# GB_TSOP44_ROM_ADAPTER_c.net
KiCad netlist of a schematic drawn in EAGLE
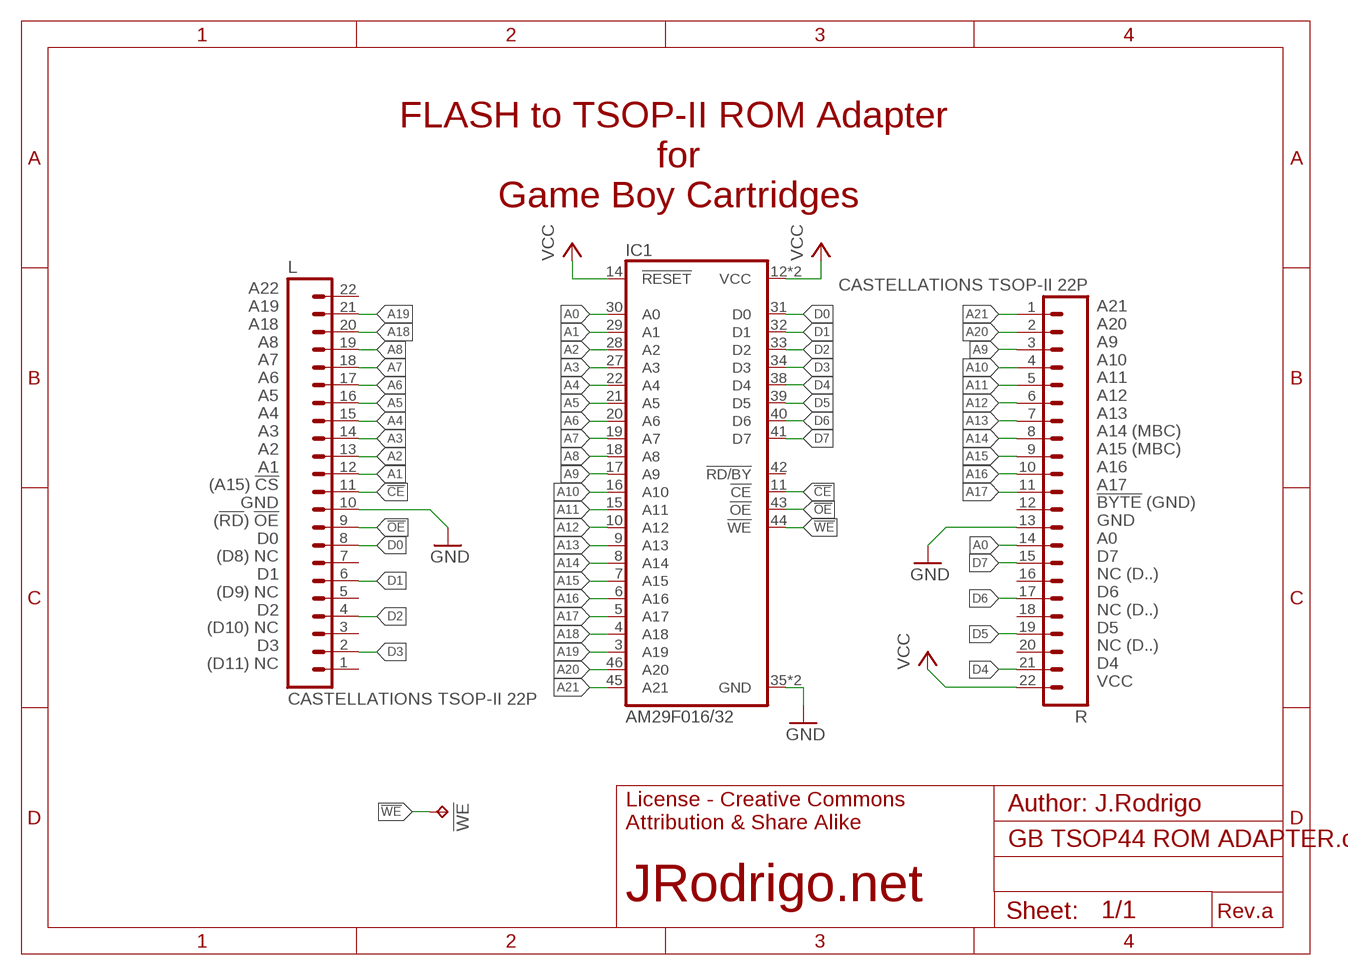
[diagram p0: schematic, sheet 1]

(export (version "E")
  (design (tool "Eeschema 10.0.6"))
  (components
    (comp (ref "!WE")
      (value "TPTP06SQ")
      (footprint "eagle-import:TP06SQ")
      (libsource (lib "eagle-import") (part "TPTP06SQ"))
    )
    (comp (ref "IC1")
      (value "AM29F016/32")
      (footprint "eagle-import:TSOP48-2")
      (libsource (lib "eagle-import") (part "AM29FXXXCUSTOM"))
    )
    (comp (ref "L")
      (value "CASTELLATIONS TSOP-II 22P")
      (footprint "eagle-import:CASTELLATIONS_TSOP_II_22PHH")
      (libsource (lib "eagle-import") (part "CASTELLATIONS_TSOP-II-22PHH"))
    )
    (comp (ref "R")
      (value "CASTELLATIONS TSOP-II 22P")
      (footprint "eagle-import:CASTELLATIONS_TSOP_II_22PHH")
      (libsource (lib "eagle-import") (part "CASTELLATIONS_TSOP-II-22PHH"))
    )
  )
  (nets
    (net (code "1") (name "/~{CE}") (class "Default")
      (node (ref "IC1") (pin "11") (pinfunction "~{CE}_11") (pintype "input"))
      (node (ref "L") (pin "11") (pinfunction "11_11") (pintype "passive"))
    )
    (net (code "2") (name "/~{OE}") (class "Default")
      (node (ref "IC1") (pin "43") (pinfunction "~{OE}_43") (pintype "input"))
      (node (ref "L") (pin "9") (pinfunction "9_9") (pintype "passive"))
    )
    (net (code "3") (name "/~{WE}") (class "Default")
      (node (ref "!WE") (pin "TP") (pinfunction "TP_TP") (pintype "input"))
      (node (ref "IC1") (pin "44") (pinfunction "~{WE}_44") (pintype "input"))
    )
    (net (code "4") (name "A0") (class "Default")
      (node (ref "IC1") (pin "30") (pinfunction "A0_30") (pintype "input"))
      (node (ref "R") (pin "14") (pinfunction "14_14") (pintype "passive"))
    )
    (net (code "5") (name "A1") (class "Default")
      (node (ref "IC1") (pin "29") (pinfunction "A1_29") (pintype "input"))
      (node (ref "L") (pin "12") (pinfunction "12_12") (pintype "passive"))
    )
    (net (code "6") (name "A2") (class "Default")
      (node (ref "IC1") (pin "28") (pinfunction "A2_28") (pintype "input"))
      (node (ref "L") (pin "13") (pinfunction "13_13") (pintype "passive"))
    )
    (net (code "7") (name "A3") (class "Default")
      (node (ref "IC1") (pin "27") (pinfunction "A3_27") (pintype "input"))
      (node (ref "L") (pin "14") (pinfunction "14_14") (pintype "passive"))
    )
    (net (code "8") (name "A4") (class "Default")
      (node (ref "IC1") (pin "22") (pinfunction "A4_22") (pintype "input"))
      (node (ref "L") (pin "15") (pinfunction "15_15") (pintype "passive"))
    )
    (net (code "9") (name "A5") (class "Default")
      (node (ref "IC1") (pin "21") (pinfunction "A5_21") (pintype "input"))
      (node (ref "L") (pin "16") (pinfunction "16_16") (pintype "passive"))
    )
    (net (code "10") (name "A6") (class "Default")
      (node (ref "IC1") (pin "20") (pinfunction "A6_20") (pintype "input"))
      (node (ref "L") (pin "17") (pinfunction "17_17") (pintype "passive"))
    )
    (net (code "11") (name "A7") (class "Default")
      (node (ref "IC1") (pin "19") (pinfunction "A7_19") (pintype "input"))
      (node (ref "L") (pin "18") (pinfunction "18_18") (pintype "passive"))
    )
    (net (code "12") (name "A8") (class "Default")
      (node (ref "IC1") (pin "18") (pinfunction "A8_18") (pintype "input"))
      (node (ref "L") (pin "19") (pinfunction "19_19") (pintype "passive"))
    )
    (net (code "13") (name "A9") (class "Default")
      (node (ref "IC1") (pin "17") (pinfunction "A9_17") (pintype "input"))
      (node (ref "R") (pin "3") (pinfunction "3_3") (pintype "passive"))
    )
    (net (code "14") (name "A10") (class "Default")
      (node (ref "IC1") (pin "16") (pinfunction "A10_16") (pintype "input"))
      (node (ref "R") (pin "4") (pinfunction "4_4") (pintype "passive"))
    )
    (net (code "15") (name "A11") (class "Default")
      (node (ref "IC1") (pin "15") (pinfunction "A11_15") (pintype "input"))
      (node (ref "R") (pin "5") (pinfunction "5_5") (pintype "passive"))
    )
    (net (code "16") (name "A12") (class "Default")
      (node (ref "IC1") (pin "10") (pinfunction "A12_10") (pintype "input"))
      (node (ref "R") (pin "6") (pinfunction "6_6") (pintype "passive"))
    )
    (net (code "17") (name "A13") (class "Default")
      (node (ref "IC1") (pin "9") (pinfunction "A13_9") (pintype "input"))
      (node (ref "R") (pin "7") (pinfunction "7_7") (pintype "passive"))
    )
    (net (code "18") (name "A14") (class "Default")
      (node (ref "IC1") (pin "8") (pinfunction "A14_8") (pintype "input"))
      (node (ref "R") (pin "8") (pinfunction "8_8") (pintype "passive"))
    )
    (net (code "19") (name "A15") (class "Default")
      (node (ref "IC1") (pin "7") (pinfunction "A15_7") (pintype "input"))
      (node (ref "R") (pin "9") (pinfunction "9_9") (pintype "passive"))
    )
    (net (code "20") (name "A16") (class "Default")
      (node (ref "IC1") (pin "6") (pinfunction "A16_6") (pintype "input"))
      (node (ref "R") (pin "10") (pinfunction "10_10") (pintype "passive"))
    )
    (net (code "21") (name "A17") (class "Default")
      (node (ref "IC1") (pin "5") (pinfunction "A17_5") (pintype "input"))
      (node (ref "R") (pin "11") (pinfunction "11_11") (pintype "passive"))
    )
    (net (code "22") (name "A18") (class "Default")
      (node (ref "IC1") (pin "4") (pinfunction "A18_4") (pintype "input"))
      (node (ref "L") (pin "20") (pinfunction "20_20") (pintype "passive"))
    )
    (net (code "23") (name "A19") (class "Default")
      (node (ref "IC1") (pin "3") (pinfunction "A19_3") (pintype "input"))
      (node (ref "L") (pin "21") (pinfunction "21_21") (pintype "passive"))
    )
    (net (code "24") (name "A20") (class "Default")
      (node (ref "IC1") (pin "46") (pinfunction "A20_46") (pintype "input"))
      (node (ref "R") (pin "2") (pinfunction "2_2") (pintype "passive"))
    )
    (net (code "25") (name "A21") (class "Default")
      (node (ref "IC1") (pin "45") (pinfunction "A21_45") (pintype "input"))
      (node (ref "R") (pin "1") (pinfunction "1_1") (pintype "passive"))
    )
    (net (code "26") (name "D0") (class "Default")
      (node (ref "IC1") (pin "31") (pinfunction "D0_31") (pintype "tri_state"))
      (node (ref "L") (pin "8") (pinfunction "8_8") (pintype "passive"))
    )
    (net (code "27") (name "D1") (class "Default")
      (node (ref "IC1") (pin "32") (pinfunction "D1_32") (pintype "tri_state"))
      (node (ref "L") (pin "6") (pinfunction "6_6") (pintype "passive"))
    )
    (net (code "28") (name "D2") (class "Default")
      (node (ref "IC1") (pin "33") (pinfunction "D2_33") (pintype "tri_state"))
      (node (ref "L") (pin "4") (pinfunction "4_4") (pintype "passive"))
    )
    (net (code "29") (name "D3") (class "Default")
      (node (ref "IC1") (pin "34") (pinfunction "D3_34") (pintype "tri_state"))
      (node (ref "L") (pin "2") (pinfunction "2_2") (pintype "passive"))
    )
    (net (code "30") (name "D4") (class "Default")
      (node (ref "IC1") (pin "38") (pinfunction "D4_38") (pintype "tri_state"))
      (node (ref "R") (pin "21") (pinfunction "21_21") (pintype "passive"))
    )
    (net (code "31") (name "D5") (class "Default")
      (node (ref "IC1") (pin "39") (pinfunction "D5_39") (pintype "tri_state"))
      (node (ref "R") (pin "19") (pinfunction "19_19") (pintype "passive"))
    )
    (net (code "32") (name "D6") (class "Default")
      (node (ref "IC1") (pin "40") (pinfunction "D6_40") (pintype "tri_state"))
      (node (ref "R") (pin "17") (pinfunction "17_17") (pintype "passive"))
    )
    (net (code "33") (name "D7") (class "Default")
      (node (ref "IC1") (pin "41") (pinfunction "D7_41") (pintype "tri_state"))
      (node (ref "R") (pin "15") (pinfunction "15_15") (pintype "passive"))
    )
    (net (code "34") (name "GND") (class "Default")
      (node (ref "IC1") (pin "35") (pinfunction "GND_35") (pintype "power_in"))
      (node (ref "IC1") (pin "36") (pinfunction "GND_36") (pintype "power_in"))
      (node (ref "L") (pin "10") (pinfunction "10_10") (pintype "passive"))
      (node (ref "R") (pin "13") (pinfunction "13_13") (pintype "passive"))
    )
    (net (code "35") (name "VCC") (class "Default")
      (node (ref "IC1") (pin "12") (pinfunction "VCC_12") (pintype "power_in"))
      (node (ref "IC1") (pin "14") (pinfunction "~{RESET}_14") (pintype "input"))
      (node (ref "IC1") (pin "37") (pinfunction "VCC_37") (pintype "power_in"))
      (node (ref "R") (pin "22") (pinfunction "22_22") (pintype "passive"))
    )
    (net (code "36") (name "unconnected-(IC1-~{RD{slash}BY}-Pad42)") (class "Default")
      (node (ref "IC1") (pin "42") (pinfunction "~{RD/BY}_42") (pintype "output"))
    )
    (net (code "37") (name "unconnected-(L-Pad1)") (class "Default")
      (node (ref "L") (pin "1") (pinfunction "1_1") (pintype "passive"))
    )
    (net (code "38") (name "unconnected-(L-Pad3)") (class "Default")
      (node (ref "L") (pin "3") (pinfunction "3_3") (pintype "passive"))
    )
    (net (code "39") (name "unconnected-(L-Pad5)") (class "Default")
      (node (ref "L") (pin "5") (pinfunction "5_5") (pintype "passive"))
    )
    (net (code "40") (name "unconnected-(L-Pad7)") (class "Default")
      (node (ref "L") (pin "7") (pinfunction "7_7") (pintype "passive"))
    )
    (net (code "41") (name "unconnected-(L-Pad22)") (class "Default")
      (node (ref "L") (pin "22") (pinfunction "22_22") (pintype "passive"))
    )
    (net (code "42") (name "unconnected-(R-Pad12)") (class "Default")
      (node (ref "R") (pin "12") (pinfunction "12_12") (pintype "passive"))
    )
    (net (code "43") (name "unconnected-(R-Pad16)") (class "Default")
      (node (ref "R") (pin "16") (pinfunction "16_16") (pintype "passive"))
    )
    (net (code "44") (name "unconnected-(R-Pad18)") (class "Default")
      (node (ref "R") (pin "18") (pinfunction "18_18") (pintype "passive"))
    )
    (net (code "45") (name "unconnected-(R-Pad20)") (class "Default")
      (node (ref "R") (pin "20") (pinfunction "20_20") (pintype "passive"))
    )
  )
)
